# Grove_-_Gas_Sensor_O2_v1_1.net
KiCad netlist of a schematic drawn in EAGLE
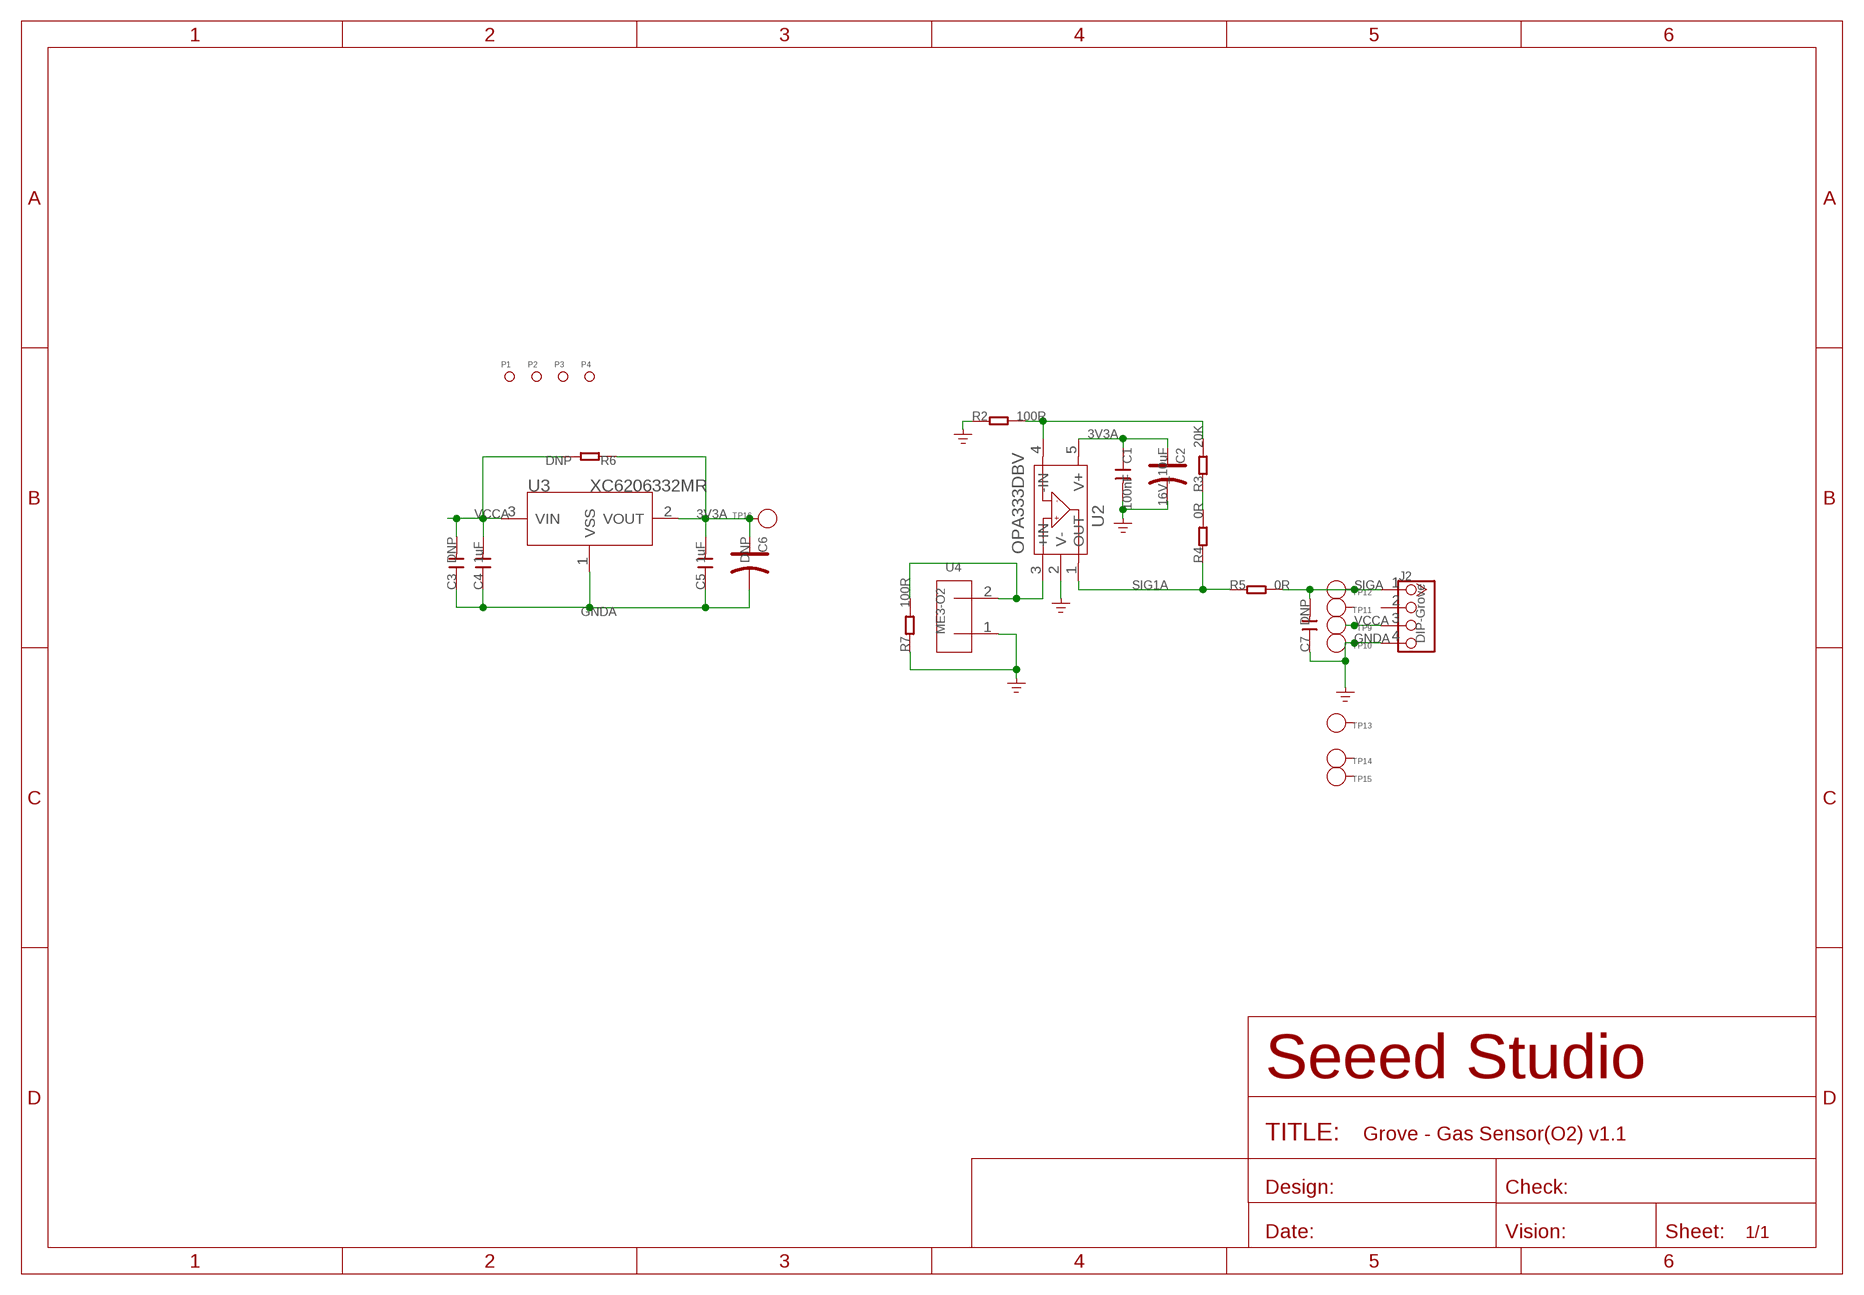
[diagram p0: schematic, sheet 1]

(export (version "E")
  (design (tool "Eeschema 10.0.6"))
  (components
    (comp (ref "C1")
      (value "100nF")
      (footprint "eagle-import:C0603")
      (libsource (lib "eagle-import") (part "C-0603"))
    )
    (comp (ref "C2")
      (value "16V_10uF")
      (footprint "eagle-import:AVX-A")
      (libsource (lib "eagle-import") (part "CAP-AVX-A"))
    )
    (comp (ref "C3")
      (value "DNP")
      (footprint "eagle-import:C0805")
      (libsource (lib "eagle-import") (part "C-0805"))
    )
    (comp (ref "C4")
      (value "1uF")
      (footprint "eagle-import:C0603")
      (libsource (lib "eagle-import") (part "C-0603"))
    )
    (comp (ref "C5")
      (value "1uF")
      (footprint "eagle-import:C0603")
      (libsource (lib "eagle-import") (part "C-0603"))
    )
    (comp (ref "C6")
      (value "DNP")
      (footprint "eagle-import:AVX-A")
      (libsource (lib "eagle-import") (part "CAP-AVX-A"))
    )
    (comp (ref "C7")
      (value "DNP")
      (footprint "eagle-import:C0805")
      (libsource (lib "eagle-import") (part "C-0805"))
    )
    (comp (ref "J2")
      (value "DIP-Grove")
      (footprint "eagle-import:4P-2.0")
      (libsource (lib "eagle-import") (part "TWIG-4P-2.0-2.0"))
    )
    (comp (ref "P1")
      (value "PAD-MARK'ANNULAR'")
      (footprint "eagle-import:ROUND-MARK-1.0")
      (fields (field (name "PARTNO") "DNP"))
      (libsource (lib "eagle-import") (part "PAD-MARK'ANNULAR'"))
    )
    (comp (ref "P2")
      (value "PAD-MARK'ANNULAR'")
      (footprint "eagle-import:ROUND-MARK-1.0")
      (fields (field (name "PARTNO") "DNP"))
      (libsource (lib "eagle-import") (part "PAD-MARK'ANNULAR'"))
    )
    (comp (ref "P3")
      (value "PAD-MARK'ANNULAR'")
      (footprint "eagle-import:ROUND-MARK-1.0")
      (fields (field (name "PARTNO") "DNP"))
      (libsource (lib "eagle-import") (part "PAD-MARK'ANNULAR'"))
    )
    (comp (ref "P4")
      (value "PAD-MARK'ANNULAR'")
      (footprint "eagle-import:ROUND-MARK-1.0")
      (fields (field (name "PARTNO") "DNP"))
      (libsource (lib "eagle-import") (part "PAD-MARK'ANNULAR'"))
    )
    (comp (ref "R2")
      (value "100R")
      (footprint "eagle-import:R0603")
      (libsource (lib "eagle-import") (part "R-0603"))
    )
    (comp (ref "R3")
      (value "20K")
      (footprint "eagle-import:R0603")
      (libsource (lib "eagle-import") (part "R-0603"))
    )
    (comp (ref "R4")
      (value "0R")
      (footprint "eagle-import:R0603")
      (libsource (lib "eagle-import") (part "R-0603"))
    )
    (comp (ref "R5")
      (value "0R")
      (footprint "eagle-import:R0603")
      (libsource (lib "eagle-import") (part "R-0603"))
    )
    (comp (ref "R6")
      (value "DNP")
      (footprint "eagle-import:R0603")
      (libsource (lib "eagle-import") (part "R-0603"))
    )
    (comp (ref "R7")
      (value "100R")
      (footprint "eagle-import:R0603")
      (libsource (lib "eagle-import") (part "R-0603"))
    )
    (comp (ref "TP9")
      (value "PAD-TEST-POINT'4545'")
      (footprint "eagle-import:TP_4545")
      (fields (field (name "PARTNO") "DNP"))
      (libsource (lib "eagle-import") (part "PAD-TEST-POINT'4545'"))
    )
    (comp (ref "TP10")
      (value "PAD-TEST-POINT'4545'")
      (footprint "eagle-import:TP_4545")
      (fields (field (name "PARTNO") "DNP"))
      (libsource (lib "eagle-import") (part "PAD-TEST-POINT'4545'"))
    )
    (comp (ref "TP11")
      (value "PAD-TEST-POINT'4545'")
      (footprint "eagle-import:TP_4545")
      (fields (field (name "PARTNO") "DNP"))
      (libsource (lib "eagle-import") (part "PAD-TEST-POINT'4545'"))
    )
    (comp (ref "TP12")
      (value "PAD-TEST-POINT'4545'")
      (footprint "eagle-import:TP_4545")
      (fields (field (name "PARTNO") "DNP"))
      (libsource (lib "eagle-import") (part "PAD-TEST-POINT'4545'"))
    )
    (comp (ref "TP13")
      (value "PAD-TEST-POINT'4545'")
      (footprint "eagle-import:TP_4545")
      (fields (field (name "PARTNO") "DNP"))
      (libsource (lib "eagle-import") (part "PAD-TEST-POINT'4545'"))
    )
    (comp (ref "TP14")
      (value "PAD-TEST-POINT'4545'")
      (footprint "eagle-import:TP_4545")
      (fields (field (name "PARTNO") "DNP"))
      (libsource (lib "eagle-import") (part "PAD-TEST-POINT'4545'"))
    )
    (comp (ref "TP15")
      (value "PAD-TEST-POINT'4545'")
      (footprint "eagle-import:TP_4545")
      (fields (field (name "PARTNO") "DNP"))
      (libsource (lib "eagle-import") (part "PAD-TEST-POINT'4545'"))
    )
    (comp (ref "TP16")
      (value "PAD-TEST-POINT'4545'")
      (footprint "eagle-import:TP_4545")
      (fields (field (name "PARTNO") "DNP"))
      (libsource (lib "eagle-import") (part "PAD-TEST-POINT'4545'"))
    )
    (comp (ref "U2")
      (value "OPA333DBV")
      (footprint "eagle-import:SOT23-5")
      (libsource (lib "eagle-import") (part "OPA333DBV"))
    )
    (comp (ref "U3")
      (value "XC6206332MR")
      (footprint "eagle-import:SOT23")
      (libsource (lib "eagle-import") (part "XC6206MR"))
    )
    (comp (ref "U4")
      (value "ME3-O2")
      (footprint "eagle-import:2P-D20X16H")
      (libsource (lib "eagle-import") (part "ME3-O2"))
    )
  )
  (nets
    (net (code "1") (name "/3V3A") (class "Default")
      (node (ref "C1") (pin "1") (pinfunction "1_1") (pintype "passive"))
      (node (ref "C2") (pin "+") (pinfunction "+_+") (pintype "passive"))
      (node (ref "C5") (pin "2") (pinfunction "2_2") (pintype "passive"))
      (node (ref "C6") (pin "+") (pinfunction "+_+") (pintype "passive"))
      (node (ref "R6") (pin "1") (pinfunction "1_1") (pintype "passive"))
      (node (ref "TP16") (pin "T") (pinfunction "T_T") (pintype "bidirectional"))
      (node (ref "U2") (pin "5") (pinfunction "V+_5") (pintype "bidirectional"))
      (node (ref "U3") (pin "2") (pinfunction "VOUT_2") (pintype "output"))
    )
    (net (code "2") (name "/SIG1A") (class "Default")
      (node (ref "R4") (pin "1") (pinfunction "1_1") (pintype "passive"))
      (node (ref "R5") (pin "1") (pinfunction "1_1") (pintype "passive"))
      (node (ref "U2") (pin "1") (pinfunction "OUT_1") (pintype "bidirectional"))
    )
    (net (code "3") (name "/SIGA") (class "Default")
      (node (ref "C7") (pin "2") (pinfunction "2_2") (pintype "passive"))
      (node (ref "J2") (pin "1") (pinfunction "1_1") (pintype "bidirectional"))
      (node (ref "R5") (pin "2") (pinfunction "2_2") (pintype "passive"))
      (node (ref "TP12") (pin "T") (pinfunction "T_T") (pintype "bidirectional"))
    )
    (net (code "4") (name "/VCCA") (class "Default")
      (node (ref "C3") (pin "2") (pinfunction "2_2") (pintype "passive"))
      (node (ref "C4") (pin "2") (pinfunction "2_2") (pintype "passive"))
      (node (ref "J2") (pin "3") (pinfunction "3_3") (pintype "bidirectional"))
      (node (ref "R6") (pin "2") (pinfunction "2_2") (pintype "passive"))
      (node (ref "TP9") (pin "T") (pinfunction "T_T") (pintype "bidirectional"))
      (node (ref "U3") (pin "3") (pinfunction "VIN_3") (pintype "input"))
    )
    (net (code "5") (name "GND_POWER") (class "Default")
      (node (ref "C1") (pin "2") (pinfunction "2_2") (pintype "passive"))
      (node (ref "C2") (pin "-") (pinfunction "-_-") (pintype "passive"))
      (node (ref "C3") (pin "1") (pinfunction "1_1") (pintype "passive"))
      (node (ref "C4") (pin "1") (pinfunction "1_1") (pintype "passive"))
      (node (ref "C5") (pin "1") (pinfunction "1_1") (pintype "passive"))
      (node (ref "C6") (pin "-") (pinfunction "-_-") (pintype "passive"))
      (node (ref "C7") (pin "1") (pinfunction "1_1") (pintype "passive"))
      (node (ref "J2") (pin "4") (pinfunction "4_4") (pintype "bidirectional"))
      (node (ref "R2") (pin "1") (pinfunction "1_1") (pintype "passive"))
      (node (ref "R7") (pin "1") (pinfunction "1_1") (pintype "passive"))
      (node (ref "TP10") (pin "T") (pinfunction "T_T") (pintype "bidirectional"))
      (node (ref "U2") (pin "2") (pinfunction "V-_2") (pintype "bidirectional"))
      (node (ref "U3") (pin "1") (pinfunction "VSS_1") (pintype "power_in"))
      (node (ref "U4") (pin "1") (pinfunction "1_1") (pintype "bidirectional"))
    )
    (net (code "6") (name "Net-(R3-Pad1)") (class "Default")
      (node (ref "R3") (pin "1") (pinfunction "1_1") (pintype "passive"))
      (node (ref "R4") (pin "2") (pinfunction "2_2") (pintype "passive"))
    )
    (net (code "7") (name "Net-(U2-+IN)") (class "Default")
      (node (ref "R7") (pin "2") (pinfunction "2_2") (pintype "passive"))
      (node (ref "U2") (pin "3") (pinfunction "+IN_3") (pintype "bidirectional"))
      (node (ref "U4") (pin "2") (pinfunction "2_2") (pintype "bidirectional"))
    )
    (net (code "8") (name "Net-(U2--IN)") (class "Default")
      (node (ref "R2") (pin "2") (pinfunction "2_2") (pintype "passive"))
      (node (ref "R3") (pin "2") (pinfunction "2_2") (pintype "passive"))
      (node (ref "U2") (pin "4") (pinfunction "-IN_4") (pintype "bidirectional"))
    )
    (net (code "9") (name "unconnected-(J2-Pad2)") (class "Default")
      (node (ref "J2") (pin "2") (pinfunction "2_2") (pintype "bidirectional"))
    )
    (net (code "10") (name "unconnected-(TP11-PadT)") (class "Default")
      (node (ref "TP11") (pin "T") (pinfunction "T_T") (pintype "bidirectional"))
    )
    (net (code "11") (name "unconnected-(TP13-PadT)") (class "Default")
      (node (ref "TP13") (pin "T") (pinfunction "T_T") (pintype "bidirectional"))
    )
    (net (code "12") (name "unconnected-(TP14-PadT)") (class "Default")
      (node (ref "TP14") (pin "T") (pinfunction "T_T") (pintype "bidirectional"))
    )
    (net (code "13") (name "unconnected-(TP15-PadT)") (class "Default")
      (node (ref "TP15") (pin "T") (pinfunction "T_T") (pintype "bidirectional"))
    )
  )
)
